# SCH_ASUS-TUF-A16-USB-HUB_2024-04-18.net
KiCad netlist of a schematic drawn in EasyEDA
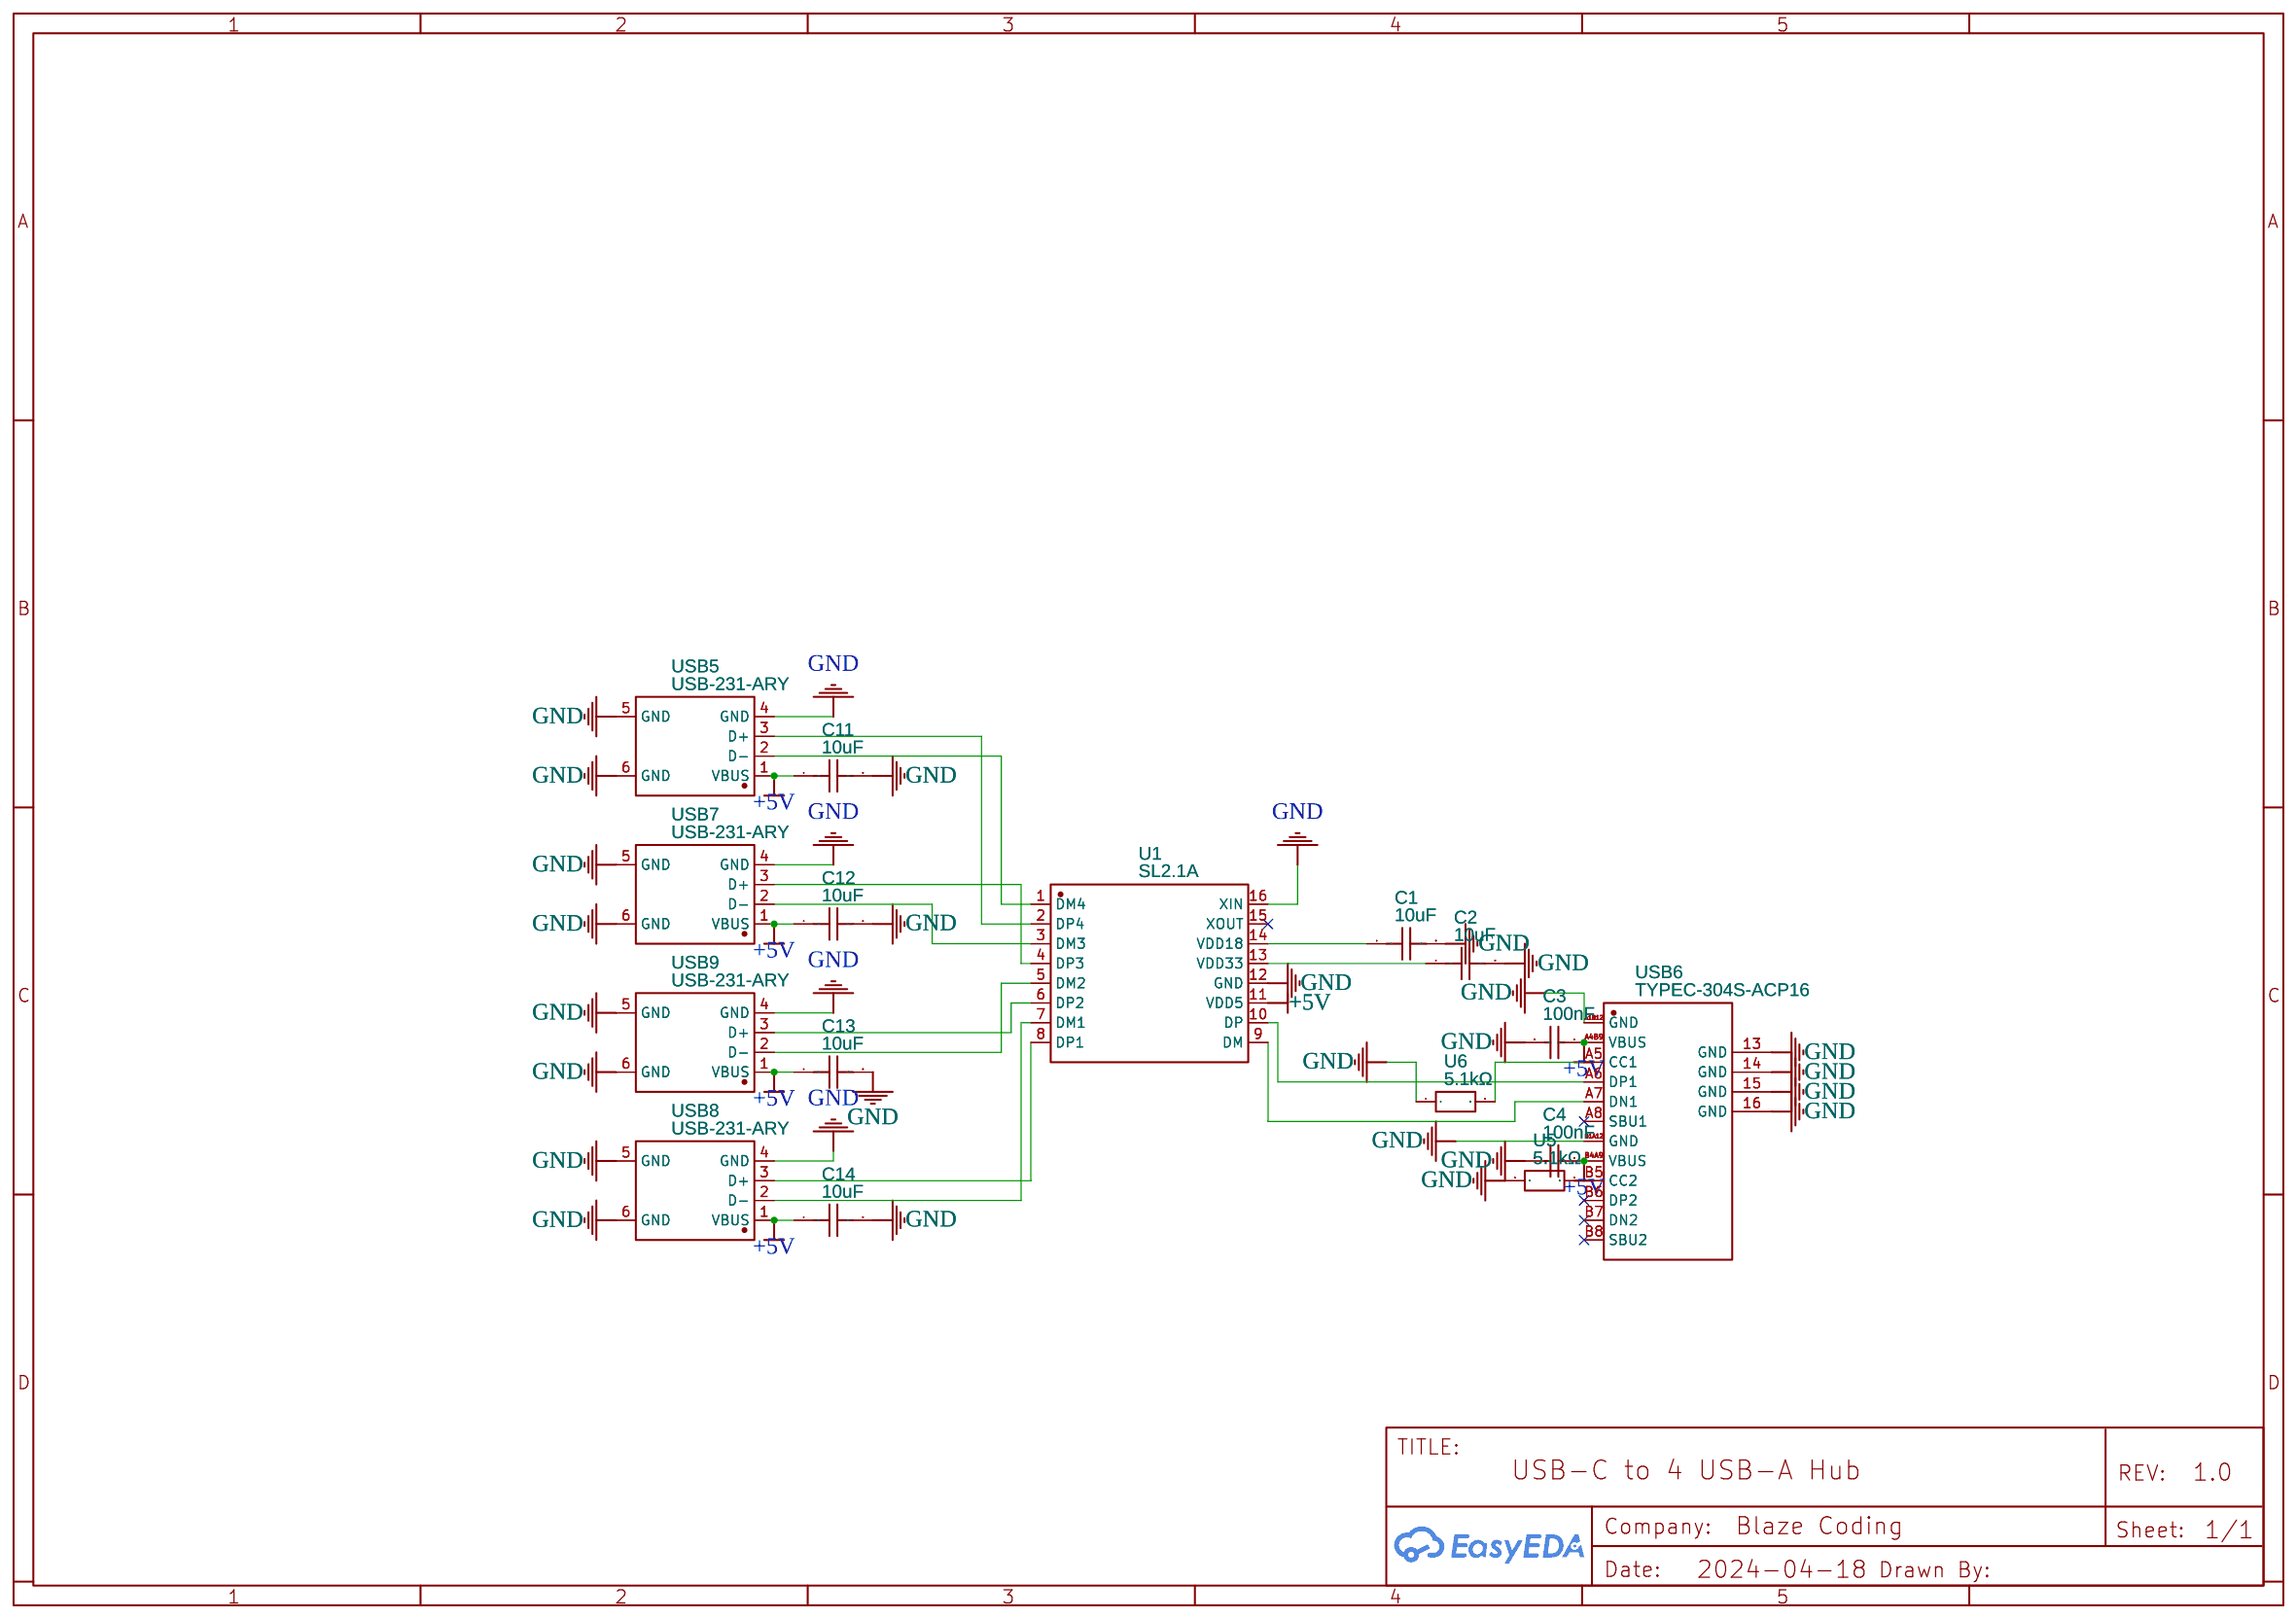
[diagram p0: schematic sheet]

(export (version "E")
  (design (tool "Eeschema 10.0.6"))
  (components
    (comp (ref "C1")
      (value "10uF")
      (fields
        (field (name "Manufacturer Part") "ZRB18AR61E106ME01L")
        (field (name "Manufacturer") "muRata(村田)")
      )
      (libsource (lib "") (part "ZRB18AR61E106ME01L"))
    )
    (comp (ref "C2")
      (value "10uF")
      (fields
        (field (name "Manufacturer Part") "ZRB18AR61E106ME01L")
        (field (name "Manufacturer") "muRata(村田)")
      )
      (libsource (lib "") (part "ZRB18AR61E106ME01L"))
    )
    (comp (ref "C3")
      (value "100nF")
      (fields
        (field (name "Manufacturer Part") "TCC0805X7R104M500DT")
        (field (name "Manufacturer") "CCTC(三环)")
      )
      (libsource (lib "") (part "TCC0805X7R104M500DT"))
    )
    (comp (ref "C4")
      (value "100nF")
      (fields
        (field (name "Manufacturer Part") "TCC0805X7R104M500DT")
        (field (name "Manufacturer") "CCTC(三环)")
      )
      (libsource (lib "") (part "TCC0805X7R104M500DT"))
    )
    (comp (ref "C11")
      (value "10uF")
      (fields
        (field (name "Manufacturer Part") "ZRB18AR61E106ME01L")
        (field (name "Manufacturer") "muRata(村田)")
      )
      (libsource (lib "") (part "ZRB18AR61E106ME01L"))
    )
    (comp (ref "C12")
      (value "10uF")
      (fields
        (field (name "Manufacturer Part") "ZRB18AR61E106ME01L")
        (field (name "Manufacturer") "muRata(村田)")
      )
      (libsource (lib "") (part "ZRB18AR61E106ME01L"))
    )
    (comp (ref "C13")
      (value "10uF")
      (fields
        (field (name "Manufacturer Part") "ZRB18AR61E106ME01L")
        (field (name "Manufacturer") "muRata(村田)")
      )
      (libsource (lib "") (part "ZRB18AR61E106ME01L"))
    )
    (comp (ref "C14")
      (value "10uF")
      (fields
        (field (name "Manufacturer Part") "ZRB18AR61E106ME01L")
        (field (name "Manufacturer") "muRata(村田)")
      )
      (libsource (lib "") (part "ZRB18AR61E106ME01L"))
    )
    (comp (ref "U1")
      (value "SL2.1A")
      (fields (field (name "Manufacturer") "CoreChips(和芯润德)"))
      (libsource (lib "") (part "SL2.1A"))
    )
    (comp (ref "U5")
      (value "5.1kΩ")
      (fields
        (field (name "Manufacturer Part") "HoARG0603-1/10W-5.1KR-0.1%-TCR25")
        (field (name "Manufacturer") "Milliohm(毫欧)")
      )
      (libsource (lib "") (part "HOARG0603-1/10W-5.1KR-0.1%-TCR25"))
    )
    (comp (ref "U6")
      (value "5.1kΩ")
      (fields
        (field (name "Manufacturer Part") "HoARG0603-1/10W-5.1KR-0.1%-TCR25")
        (field (name "Manufacturer") "Milliohm(毫欧)")
      )
      (libsource (lib "") (part "HOARG0603-1/10W-5.1KR-0.1%-TCR25"))
    )
    (comp (ref "USB5")
      (value "USB-231-ARY")
      (fields (field (name "Manufacturer") "XUNPU(讯普)"))
      (libsource (lib "") (part "USB-231-ARY"))
    )
    (comp (ref "USB6")
      (value "TYPEC-304S-ACP16")
      (fields (field (name "Manufacturer") "XUNPU(讯普)"))
      (libsource (lib "") (part "TYPEC-304S-ACP16"))
    )
    (comp (ref "USB7")
      (value "USB-231-ARY")
      (fields (field (name "Manufacturer") "XUNPU(讯普)"))
      (libsource (lib "") (part "USB-231-ARY"))
    )
    (comp (ref "USB8")
      (value "USB-231-ARY")
      (fields (field (name "Manufacturer") "XUNPU(讯普)"))
      (libsource (lib "") (part "USB-231-ARY"))
    )
    (comp (ref "USB9")
      (value "USB-231-ARY")
      (fields (field (name "Manufacturer") "XUNPU(讯普)"))
      (libsource (lib "") (part "USB-231-ARY"))
    )
  )
  (nets
    (net (code "1") (name "+5V") (class "Default")
      (node (ref "C11") (pin "1") (pinfunction "1_1") (pintype "unspecified"))
      (node (ref "C12") (pin "1") (pinfunction "1_1") (pintype "unspecified"))
      (node (ref "C13") (pin "1") (pinfunction "1_1") (pintype "unspecified"))
      (node (ref "C14") (pin "1") (pinfunction "1_1") (pintype "unspecified"))
      (node (ref "C3") (pin "1") (pinfunction "1_1") (pintype "input"))
      (node (ref "C4") (pin "1") (pinfunction "1_1") (pintype "input"))
      (node (ref "U1") (pin "11") (pinfunction "VDD5_11") (pintype "unspecified"))
      (node (ref "USB5") (pin "1") (pinfunction "VBUS_1") (pintype "unspecified"))
      (node (ref "USB6") (pin "A4B9") (pinfunction "VBUS_A4B9") (pintype "unspecified"))
      (node (ref "USB6") (pin "B4A9") (pinfunction "VBUS_B4A9") (pintype "unspecified"))
      (node (ref "USB7") (pin "1") (pinfunction "VBUS_1") (pintype "unspecified"))
      (node (ref "USB8") (pin "1") (pinfunction "VBUS_1") (pintype "unspecified"))
      (node (ref "USB9") (pin "1") (pinfunction "VBUS_1") (pintype "unspecified"))
    )
    (net (code "2") (name "GND") (class "Default")
      (node (ref "C1") (pin "2") (pinfunction "2_2") (pintype "unspecified"))
      (node (ref "C11") (pin "2") (pinfunction "2_2") (pintype "unspecified"))
      (node (ref "C12") (pin "2") (pinfunction "2_2") (pintype "unspecified"))
      (node (ref "C13") (pin "2") (pinfunction "2_2") (pintype "unspecified"))
      (node (ref "C14") (pin "2") (pinfunction "2_2") (pintype "unspecified"))
      (node (ref "C2") (pin "2") (pinfunction "2_2") (pintype "unspecified"))
      (node (ref "C3") (pin "2") (pinfunction "2_2") (pintype "input"))
      (node (ref "C4") (pin "2") (pinfunction "2_2") (pintype "input"))
      (node (ref "U1") (pin "12") (pinfunction "GND_12") (pintype "unspecified"))
      (node (ref "U1") (pin "16") (pinfunction "XIN_16") (pintype "unspecified"))
      (node (ref "U5") (pin "1") (pinfunction "1_1") (pintype "unspecified"))
      (node (ref "U6") (pin "1") (pinfunction "1_1") (pintype "unspecified"))
      (node (ref "USB5") (pin "4") (pinfunction "GND_4") (pintype "unspecified"))
      (node (ref "USB5") (pin "5") (pinfunction "GND_5") (pintype "unspecified"))
      (node (ref "USB5") (pin "6") (pinfunction "GND_6") (pintype "unspecified"))
      (node (ref "USB6") (pin "13") (pinfunction "GND_13") (pintype "unspecified"))
      (node (ref "USB6") (pin "14") (pinfunction "GND_14") (pintype "unspecified"))
      (node (ref "USB6") (pin "15") (pinfunction "GND_15") (pintype "unspecified"))
      (node (ref "USB6") (pin "16") (pinfunction "GND_16") (pintype "unspecified"))
      (node (ref "USB6") (pin "A1B12") (pinfunction "GND_A1B12") (pintype "unspecified"))
      (node (ref "USB6") (pin "B1A12") (pinfunction "GND_B1A12") (pintype "unspecified"))
      (node (ref "USB7") (pin "4") (pinfunction "GND_4") (pintype "unspecified"))
      (node (ref "USB7") (pin "5") (pinfunction "GND_5") (pintype "unspecified"))
      (node (ref "USB7") (pin "6") (pinfunction "GND_6") (pintype "unspecified"))
      (node (ref "USB8") (pin "4") (pinfunction "GND_4") (pintype "unspecified"))
      (node (ref "USB8") (pin "5") (pinfunction "GND_5") (pintype "unspecified"))
      (node (ref "USB8") (pin "6") (pinfunction "GND_6") (pintype "unspecified"))
      (node (ref "USB9") (pin "4") (pinfunction "GND_4") (pintype "unspecified"))
      (node (ref "USB9") (pin "5") (pinfunction "GND_5") (pintype "unspecified"))
      (node (ref "USB9") (pin "6") (pinfunction "GND_6") (pintype "unspecified"))
    )
    (net (code "3") (name "Net-(U1-DM)") (class "Default")
      (node (ref "U1") (pin "9") (pinfunction "DM_9") (pintype "unspecified"))
      (node (ref "USB6") (pin "A7") (pinfunction "DN1_A7") (pintype "unspecified"))
    )
    (net (code "4") (name "Net-(U1-DM1)") (class "Default")
      (node (ref "U1") (pin "7") (pinfunction "DM1_7") (pintype "unspecified"))
      (node (ref "USB8") (pin "2") (pinfunction "D-_2") (pintype "unspecified"))
    )
    (net (code "5") (name "Net-(U1-DM2)") (class "Default")
      (node (ref "U1") (pin "5") (pinfunction "DM2_5") (pintype "unspecified"))
      (node (ref "USB9") (pin "2") (pinfunction "D-_2") (pintype "unspecified"))
    )
    (net (code "6") (name "Net-(U1-DM3)") (class "Default")
      (node (ref "U1") (pin "3") (pinfunction "DM3_3") (pintype "unspecified"))
      (node (ref "USB7") (pin "2") (pinfunction "D-_2") (pintype "unspecified"))
    )
    (net (code "7") (name "Net-(U1-DM4)") (class "Default")
      (node (ref "U1") (pin "1") (pinfunction "DM4_1") (pintype "unspecified"))
      (node (ref "USB5") (pin "2") (pinfunction "D-_2") (pintype "unspecified"))
    )
    (net (code "8") (name "Net-(U1-DP)") (class "Default")
      (node (ref "U1") (pin "10") (pinfunction "DP_10") (pintype "unspecified"))
      (node (ref "USB6") (pin "A6") (pinfunction "DP1_A6") (pintype "unspecified"))
    )
    (net (code "9") (name "Net-(U1-DP1)") (class "Default")
      (node (ref "U1") (pin "8") (pinfunction "DP1_8") (pintype "unspecified"))
      (node (ref "USB8") (pin "3") (pinfunction "D+_3") (pintype "unspecified"))
    )
    (net (code "10") (name "Net-(U1-DP2)") (class "Default")
      (node (ref "U1") (pin "6") (pinfunction "DP2_6") (pintype "unspecified"))
      (node (ref "USB9") (pin "3") (pinfunction "D+_3") (pintype "unspecified"))
    )
    (net (code "11") (name "Net-(U1-DP3)") (class "Default")
      (node (ref "U1") (pin "4") (pinfunction "DP3_4") (pintype "unspecified"))
      (node (ref "USB7") (pin "3") (pinfunction "D+_3") (pintype "unspecified"))
    )
    (net (code "12") (name "Net-(U1-DP4)") (class "Default")
      (node (ref "U1") (pin "2") (pinfunction "DP4_2") (pintype "unspecified"))
      (node (ref "USB5") (pin "3") (pinfunction "D+_3") (pintype "unspecified"))
    )
    (net (code "13") (name "Net-(U1-VDD18)") (class "Default")
      (node (ref "C1") (pin "1") (pinfunction "1_1") (pintype "unspecified"))
      (node (ref "U1") (pin "14") (pinfunction "VDD18_14") (pintype "unspecified"))
    )
    (net (code "14") (name "Net-(U1-VDD33)") (class "Default")
      (node (ref "C2") (pin "1") (pinfunction "1_1") (pintype "unspecified"))
      (node (ref "U1") (pin "13") (pinfunction "VDD33_13") (pintype "unspecified"))
    )
    (net (code "15") (name "Net-(USB6-CC1)") (class "Default")
      (node (ref "U6") (pin "2") (pinfunction "2_2") (pintype "unspecified"))
      (node (ref "USB6") (pin "A5") (pinfunction "CC1_A5") (pintype "unspecified"))
    )
    (net (code "16") (name "Net-(USB6-CC2)") (class "Default")
      (node (ref "U5") (pin "2") (pinfunction "2_2") (pintype "unspecified"))
      (node (ref "USB6") (pin "B5") (pinfunction "CC2_B5") (pintype "unspecified"))
    )
    (net (code "17") (name "unconnected-(U1-XOUT-Pad15)") (class "Default")
      (node (ref "U1") (pin "15") (pinfunction "XOUT_15") (pintype "unspecified+no_connect"))
    )
    (net (code "18") (name "unconnected-(USB6-DN2-PadB7)") (class "Default")
      (node (ref "USB6") (pin "B7") (pinfunction "DN2_B7") (pintype "unspecified+no_connect"))
    )
    (net (code "19") (name "unconnected-(USB6-DP2-PadB6)") (class "Default")
      (node (ref "USB6") (pin "B6") (pinfunction "DP2_B6") (pintype "unspecified+no_connect"))
    )
    (net (code "20") (name "unconnected-(USB6-SBU1-PadA8)") (class "Default")
      (node (ref "USB6") (pin "A8") (pinfunction "SBU1_A8") (pintype "unspecified+no_connect"))
    )
    (net (code "21") (name "unconnected-(USB6-SBU2-PadB8)") (class "Default")
      (node (ref "USB6") (pin "B8") (pinfunction "SBU2_B8") (pintype "unspecified+no_connect"))
    )
  )
)
